# mapleCUx_large_340b-008.net
KiCad netlist of a schematic drawn in EAGLE
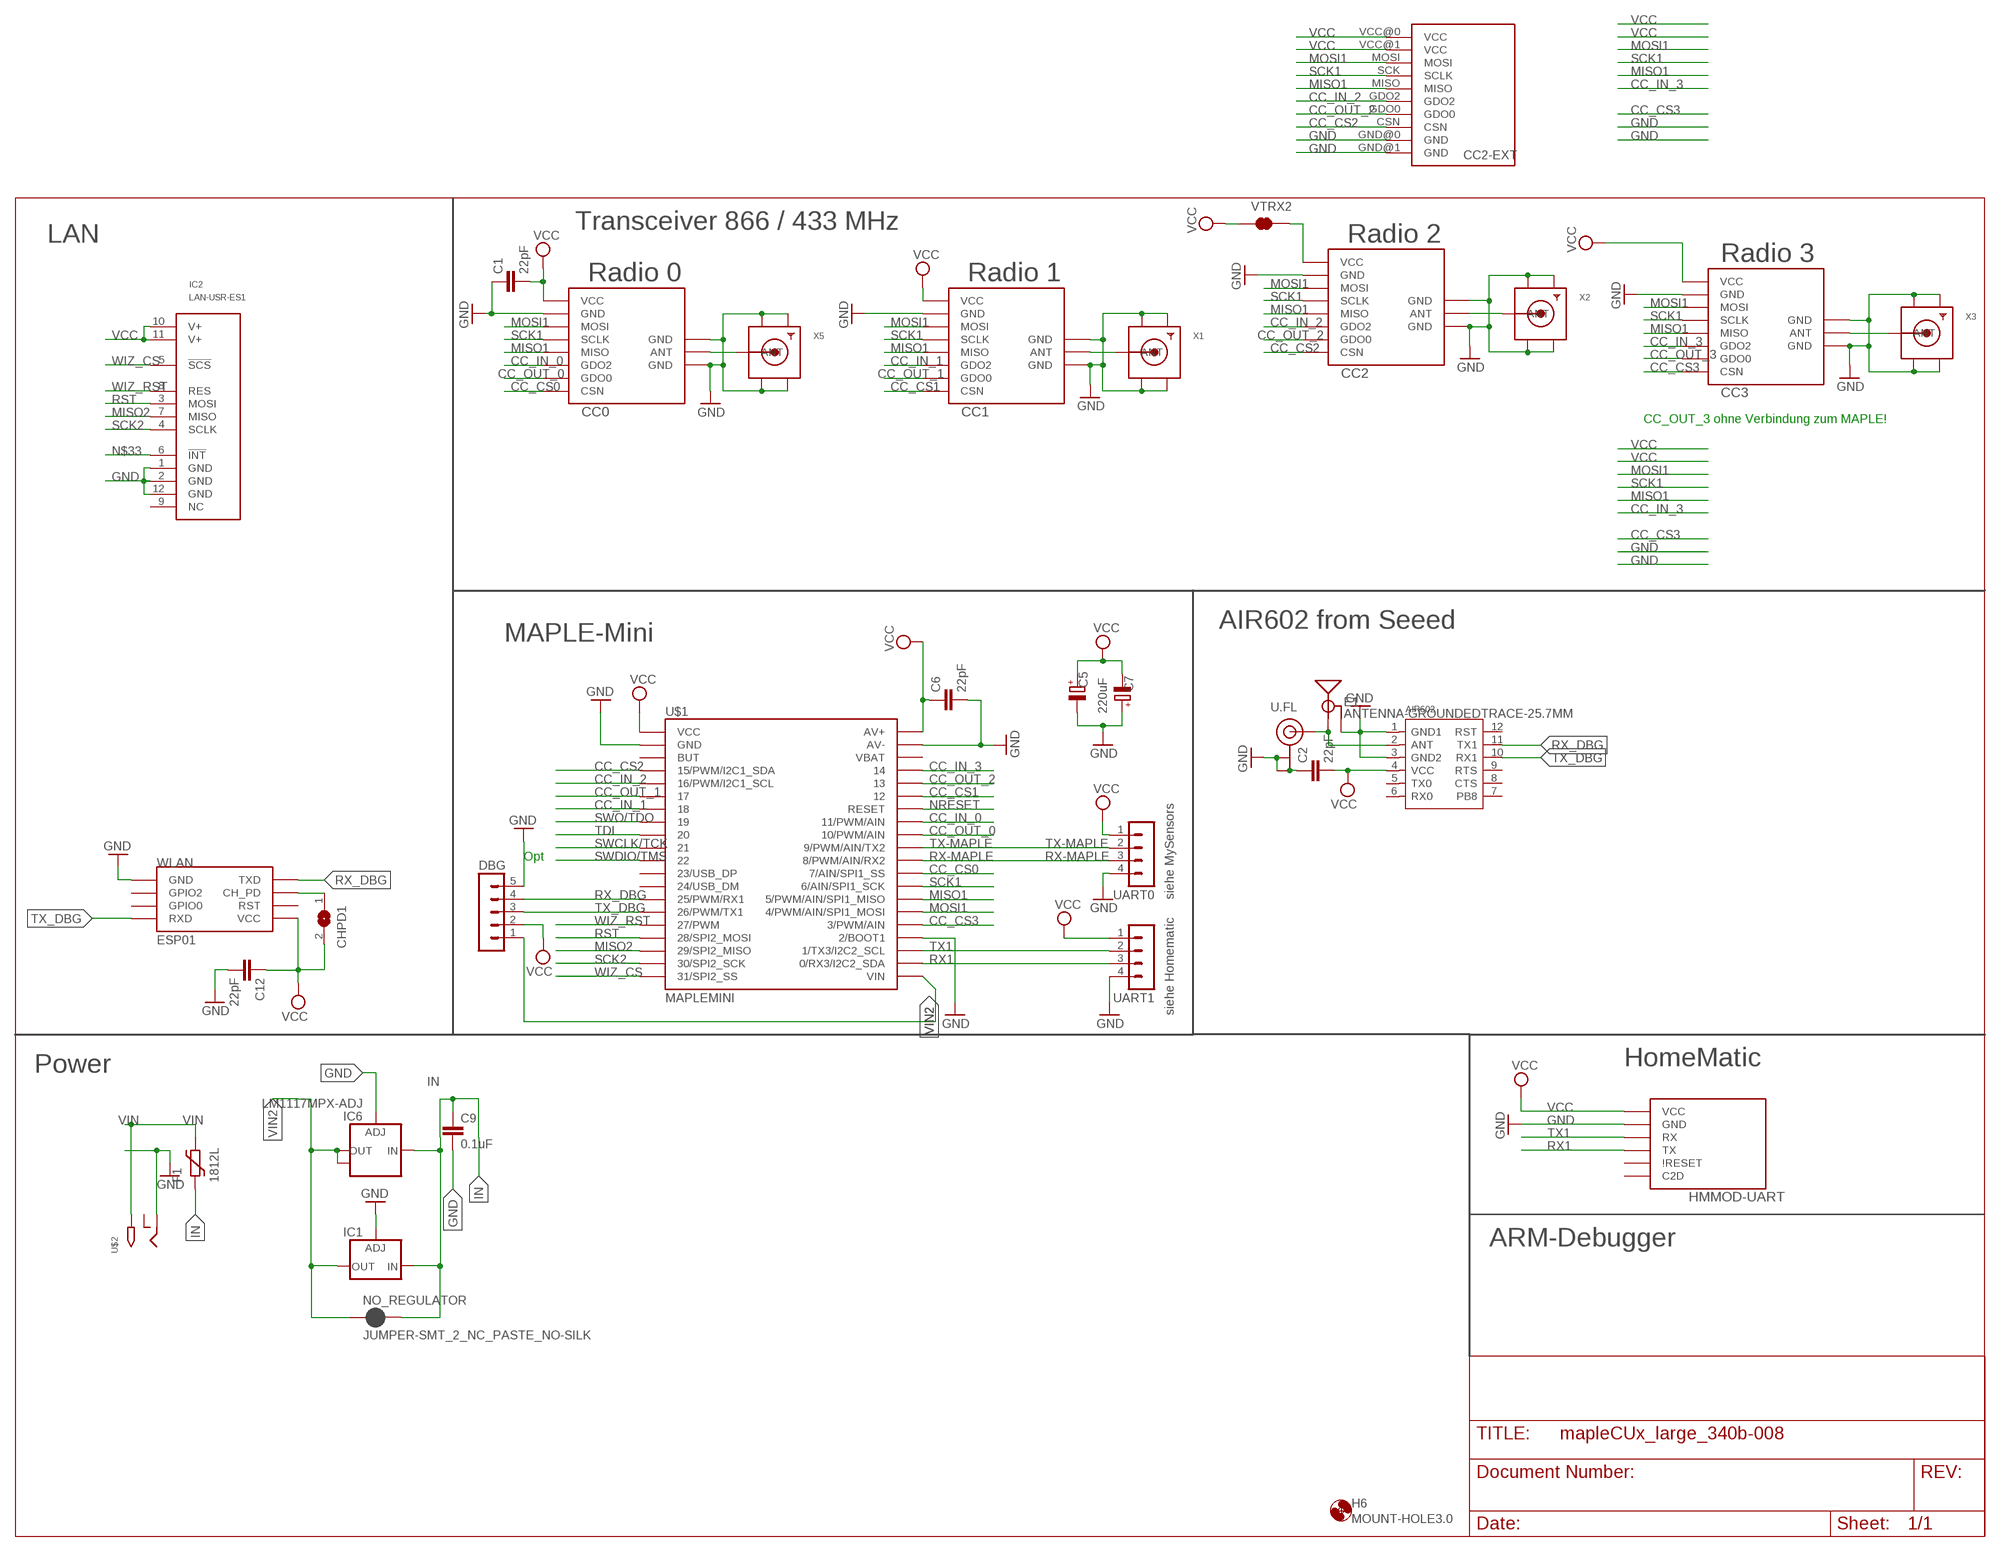
[diagram p0: schematic, sheet 1]

(export (version "E")
  (design (tool "Eeschema 10.0.6"))
  (components
    (comp (ref "AIR602")
      (value "AIR602")
      (footprint "eagle-import:MODULE12P-2.0-10X12MM")
      (libsource (lib "eagle-import") (part "AIR602"))
    )
    (comp (ref "C1")
      (value "22pF")
      (footprint "eagle-import:C0805")
      (libsource (lib "eagle-import") (part "C-EUC0805"))
    )
    (comp (ref "C2")
      (value "22pF")
      (footprint "eagle-import:C0805")
      (libsource (lib "eagle-import") (part "C-EUC0805"))
    )
    (comp (ref "C5")
      (value "220uF")
      (footprint "eagle-import:E5-8,5")
      (libsource (lib "eagle-import") (part "CPOL-EUE5-8.5"))
    )
    (comp (ref "C6")
      (value "22pF")
      (footprint "eagle-import:C0805")
      (libsource (lib "eagle-import") (part "C-EUC0805"))
    )
    (comp (ref "C7")
      (value "CPOL-EUSMCE")
      (footprint "eagle-import:SMC_E")
      (libsource (lib "eagle-import") (part "rcl_334_CPOL-EUSMCE"))
    )
    (comp (ref "C9")
      (value "0.1uF")
      (footprint "eagle-import:C1206")
      (libsource (lib "eagle-import") (part "C-EUC1206"))
    )
    (comp (ref "C12")
      (value "22pF")
      (footprint "eagle-import:C0805")
      (libsource (lib "eagle-import") (part "C-EUC0805"))
    )
    (comp (ref "CC0")
      (value "CC1101")
      (footprint "eagle-import:CC1101_MODULE1_SMD")
      (libsource (lib "eagle-import") (part "CC1101_MODULE1SMD"))
    )
    (comp (ref "CC1")
      (value "CC1101_MODULE1SMD")
      (footprint "eagle-import:CC1101_MODULE1_SMD")
      (libsource (lib "eagle-import") (part "CC1101_MODULE1SMD"))
    )
    (comp (ref "CC2")
      (value "CC1101_MODULE1SMD")
      (footprint "eagle-import:CC1101_MODULE1_SMD")
      (libsource (lib "eagle-import") (part "CC1101_MODULE1SMD"))
    )
    (comp (ref "CC2-EXT")
      (value "CC1101_MODULE3_DIL")
      (footprint "eagle-import:CC1101_MODULE3_DIL")
      (libsource (lib "eagle-import") (part "CC1101_MODULE3_DIL"))
    )
    (comp (ref "CC3")
      (value "CC1101_MODULE1SMD")
      (footprint "eagle-import:CC1101_MODULE1_SMD")
      (libsource (lib "eagle-import") (part "CC1101_MODULE1SMD"))
    )
    (comp (ref "CHPD1")
      (value "SJ")
      (footprint "eagle-import:SJ")
      (libsource (lib "eagle-import") (part "SJ"))
    )
    (comp (ref "DBG")
      (value "MA05-1")
      (footprint "eagle-import:MA05-1")
      (libsource (lib "eagle-import") (part "MA05-1"))
    )
    (comp (ref "E1")
      (value "ANTENNA-GROUNDEDTRACE-25.7MM")
      (footprint "eagle-import:TRACE_ANTENNA_2.4GHZ_25.7MM")
      (libsource (lib "eagle-import") (part "ANTENNA-GROUNDEDTRACE-25.7MM"))
    )
    (comp (ref "F1")
      (value "1812L")
      (footprint "eagle-import:1812L")
      (libsource (lib "eagle-import") (part "1812L"))
    )
    (comp (ref "H6")
      (value "MOUNT-HOLE3.0")
      (footprint "eagle-import:3,0")
      (libsource (lib "eagle-import") (part "MOUNT-HOLE3.0"))
    )
    (comp (ref "HMMOD-UART")
      (value "HM-MOD-UARTDIL")
      (footprint "eagle-import:HM-MOD-UART-DIL")
      (libsource (lib "eagle-import") (part "HM-MOD-UARTDIL"))
    )
    (comp (ref "IC1")
      (value "LD117ADT50TR")
      (footprint "eagle-import:DPACK")
      (libsource (lib "eagle-import") (part "LD117A?DT50TR"))
    )
    (comp (ref "IC2")
      (value "LAN-USR-ES1")
      (footprint "eagle-import:USR-ES1")
      (libsource (lib "eagle-import") (part "LAN-USR-ES1"))
    )
    (comp (ref "IC6")
      (value "LM1117MPX-ADJ")
      (footprint "eagle-import:SOT223")
      (libsource (lib "eagle-import") (part "LM1117MPX-ADJ"))
    )
    (comp (ref "NO_REGULATOR")
      (value "JUMPER-SMT_2_NC_PASTE_NO-SILK")
      (footprint "eagle-import:SMT-JUMPER_2_NC_PASTE_NO-SILK")
      (libsource (lib "eagle-import") (part "JUMPER-SMT_2_NC_PASTE_NO-SILK"))
    )
    (comp (ref "U$1")
      (value "MAPLEMINI")
      (footprint "eagle-import:20-DIP")
      (libsource (lib "eagle-import") (part "MAPLEMINI"))
    )
    (comp (ref "U$2")
      (value "2.1MMJACKTHM")
      (footprint "eagle-import:PJ-102A")
      (libsource (lib "eagle-import") (part "2.1MMJACKTHM"))
    )
    (comp (ref "U.FL")
      (value "U.FL")
      (footprint "eagle-import:U.FL")
      (libsource (lib "eagle-import") (part "U.FL"))
    )
    (comp (ref "UART0")
      (value "MA04-1")
      (footprint "eagle-import:MA04-1")
      (libsource (lib "eagle-import") (part "MA04-1"))
    )
    (comp (ref "UART1")
      (value "MA04-1")
      (footprint "eagle-import:MA04-1")
      (libsource (lib "eagle-import") (part "MA04-1"))
    )
    (comp (ref "VTRX2")
      (value "JUMPER-SMT_2_NC_TRACE_SILK")
      (footprint "eagle-import:SMT-JUMPER_2_NC_TRACE_SILK")
      (libsource (lib "eagle-import") (part "JUMPER-SMT_2_NC_TRACE_SILK"))
    )
    (comp (ref "WLAN")
      (value "ESP01")
      (footprint "eagle-import:ESP01")
      (libsource (lib "eagle-import") (part "ESP01"))
    )
    (comp (ref "X1")
      (value "SMACONNECTOR_EDGE")
      (footprint "eagle-import:SMA_EDGELAUNCH")
      (libsource (lib "eagle-import") (part "SMACONNECTOR_EDGE"))
    )
    (comp (ref "X2")
      (value "SMACONNECTOR_EDGE")
      (footprint "eagle-import:SMA_EDGELAUNCH")
      (libsource (lib "eagle-import") (part "SMACONNECTOR_EDGE"))
    )
    (comp (ref "X3")
      (value "SMACONNECTOR_EDGE")
      (footprint "eagle-import:SMA_EDGELAUNCH")
      (libsource (lib "eagle-import") (part "SMACONNECTOR_EDGE"))
    )
    (comp (ref "X5")
      (value "SMACONNECTOR_EDGE")
      (footprint "eagle-import:SMA_EDGELAUNCH")
      (libsource (lib "eagle-import") (part "SMACONNECTOR_EDGE"))
    )
  )
  (nets
    (net (code "1") (name "/CC_CS0") (class "Default")
      (node (ref "CC0") (pin "CSN") (pinfunction "CSN_CSN") (pintype "bidirectional"))
      (node (ref "U$1") (pin "29") (pinfunction "7/AIN/SPI1_SS_29") (pintype "bidirectional"))
    )
    (net (code "2") (name "/CC_CS1") (class "Default")
      (node (ref "CC1") (pin "CSN") (pinfunction "CSN_CSN") (pintype "bidirectional"))
      (node (ref "U$1") (pin "35") (pinfunction "12_35") (pintype "bidirectional"))
    )
    (net (code "3") (name "/CC_CS2") (class "Default")
      (node (ref "CC2") (pin "CSN") (pinfunction "CSN_CSN") (pintype "bidirectional"))
      (node (ref "CC2-EXT") (pin "CSN") (pinfunction "CSN_CSN") (pintype "bidirectional"))
      (node (ref "U$1") (pin "4") (pinfunction "15/PWM/I2C1_SDA_4") (pintype "bidirectional"))
    )
    (net (code "4") (name "/CC_CS3") (class "Default")
      (node (ref "CC3") (pin "CSN") (pinfunction "CSN_CSN") (pintype "bidirectional"))
      (node (ref "U$1") (pin "25") (pinfunction "3/PWM/AIN_25") (pintype "bidirectional"))
    )
    (net (code "5") (name "/CC_IN_0") (class "Default")
      (node (ref "CC0") (pin "GDO2") (pinfunction "GDO2_GDO2") (pintype "bidirectional"))
      (node (ref "U$1") (pin "33") (pinfunction "11/PWM/AIN_33") (pintype "bidirectional"))
    )
    (net (code "6") (name "/CC_IN_1") (class "Default")
      (node (ref "CC1") (pin "GDO2") (pinfunction "GDO2_GDO2") (pintype "bidirectional"))
      (node (ref "U$1") (pin "7") (pinfunction "18_7") (pintype "bidirectional"))
    )
    (net (code "7") (name "/CC_IN_2") (class "Default")
      (node (ref "CC2") (pin "GDO2") (pinfunction "GDO2_GDO2") (pintype "bidirectional"))
      (node (ref "CC2-EXT") (pin "GDO2") (pinfunction "GDO2_GDO2") (pintype "bidirectional"))
      (node (ref "U$1") (pin "5") (pinfunction "16/PWM/I2C1_SCL_5") (pintype "bidirectional"))
    )
    (net (code "8") (name "/CC_IN_3") (class "Default")
      (node (ref "CC3") (pin "GDO2") (pinfunction "GDO2_GDO2") (pintype "bidirectional"))
      (node (ref "U$1") (pin "37") (pinfunction "14_37") (pintype "bidirectional"))
    )
    (net (code "9") (name "/CC_OUT_0") (class "Default")
      (node (ref "CC0") (pin "GDO0") (pinfunction "GDO0_GDO0") (pintype "bidirectional"))
      (node (ref "U$1") (pin "32") (pinfunction "10/PWM/AIN_32") (pintype "bidirectional"))
    )
    (net (code "10") (name "/CC_OUT_1") (class "Default")
      (node (ref "CC1") (pin "GDO0") (pinfunction "GDO0_GDO0") (pintype "bidirectional"))
      (node (ref "U$1") (pin "6") (pinfunction "17_6") (pintype "bidirectional"))
    )
    (net (code "11") (name "/CC_OUT_2") (class "Default")
      (node (ref "CC2") (pin "GDO0") (pinfunction "GDO0_GDO0") (pintype "bidirectional"))
      (node (ref "CC2-EXT") (pin "GDO0") (pinfunction "GDO0_GDO0") (pintype "bidirectional"))
      (node (ref "U$1") (pin "36") (pinfunction "13_36") (pintype "bidirectional"))
    )
    (net (code "12") (name "/CC_OUT_3") (class "Default")
      (node (ref "CC3") (pin "GDO0") (pinfunction "GDO0_GDO0") (pintype "bidirectional"))
    )
    (net (code "13") (name "/MISO1") (class "Default")
      (node (ref "CC0") (pin "MISO") (pinfunction "MISO_MISO") (pintype "bidirectional"))
      (node (ref "CC1") (pin "MISO") (pinfunction "MISO_MISO") (pintype "bidirectional"))
      (node (ref "CC2") (pin "MISO") (pinfunction "MISO_MISO") (pintype "bidirectional"))
      (node (ref "CC2-EXT") (pin "MISO") (pinfunction "MISO_MISO") (pintype "bidirectional"))
      (node (ref "CC3") (pin "MISO") (pinfunction "MISO_MISO") (pintype "bidirectional"))
      (node (ref "U$1") (pin "27") (pinfunction "5/PWM/AIN/SPI1_MISO_27") (pintype "bidirectional"))
    )
    (net (code "14") (name "/MISO2") (class "Default")
      (node (ref "IC2") (pin "7") (pinfunction "MISO_7") (pintype "bidirectional"))
      (node (ref "U$1") (pin "18") (pinfunction "29/SPI2_MISO_18") (pintype "bidirectional"))
    )
    (net (code "15") (name "/MOSI1") (class "Default")
      (node (ref "CC0") (pin "MOSI") (pinfunction "MOSI_MOSI") (pintype "bidirectional"))
      (node (ref "CC1") (pin "MOSI") (pinfunction "MOSI_MOSI") (pintype "bidirectional"))
      (node (ref "CC2") (pin "MOSI") (pinfunction "MOSI_MOSI") (pintype "bidirectional"))
      (node (ref "CC2-EXT") (pin "MOSI") (pinfunction "MOSI_MOSI") (pintype "bidirectional"))
      (node (ref "CC3") (pin "MOSI") (pinfunction "MOSI_MOSI") (pintype "bidirectional"))
      (node (ref "U$1") (pin "26") (pinfunction "4/PWM/AIN/SPI1_MOSI_26") (pintype "bidirectional"))
    )
    (net (code "16") (name "/N$33") (class "Default")
      (node (ref "IC2") (pin "6") (pinfunction "~{INT}_6") (pintype "output"))
    )
    (net (code "17") (name "/NRESET") (class "Default")
      (node (ref "U$1") (pin "34") (pinfunction "RESET_34") (pintype "bidirectional"))
    )
    (net (code "18") (name "/RST") (class "Default")
      (node (ref "IC2") (pin "3") (pinfunction "MOSI_3") (pintype "bidirectional"))
      (node (ref "U$1") (pin "17") (pinfunction "28/SPI2_MOSI_17") (pintype "bidirectional"))
    )
    (net (code "19") (name "/RX-MAPLE") (class "Default")
      (node (ref "U$1") (pin "30") (pinfunction "8/PWM/AIN/RX2_30") (pintype "bidirectional"))
      (node (ref "UART0") (pin "3") (pinfunction "3_3") (pintype "passive"))
    )
    (net (code "20") (name "/RX1") (class "Default")
      (node (ref "HMMOD-UART") (pin "5") (pinfunction "TX_5") (pintype "bidirectional"))
      (node (ref "U$1") (pin "22") (pinfunction "0/RX3/I2C2_SDA_22") (pintype "bidirectional"))
      (node (ref "UART1") (pin "3") (pinfunction "3_3") (pintype "passive"))
    )
    (net (code "21") (name "/SCK1") (class "Default")
      (node (ref "CC0") (pin "SCLK") (pinfunction "SCLK_SCLK") (pintype "bidirectional"))
      (node (ref "CC1") (pin "SCLK") (pinfunction "SCLK_SCLK") (pintype "bidirectional"))
      (node (ref "CC2") (pin "SCLK") (pinfunction "SCLK_SCLK") (pintype "bidirectional"))
      (node (ref "CC2-EXT") (pin "SCK") (pinfunction "SCLK_SCK") (pintype "bidirectional"))
      (node (ref "CC3") (pin "SCLK") (pinfunction "SCLK_SCLK") (pintype "bidirectional"))
      (node (ref "U$1") (pin "28") (pinfunction "6/AIN/SPI1_SCK_28") (pintype "bidirectional"))
    )
    (net (code "22") (name "/SCK2") (class "Default")
      (node (ref "IC2") (pin "4") (pinfunction "SCLK_4") (pintype "input"))
      (node (ref "U$1") (pin "19") (pinfunction "30/SPI2_SCK_19") (pintype "bidirectional"))
    )
    (net (code "23") (name "/SWCLK{slash}TCK") (class "Default")
      (node (ref "U$1") (pin "10") (pinfunction "21_10") (pintype "bidirectional"))
    )
    (net (code "24") (name "/SWDIO{slash}TMS") (class "Default")
      (node (ref "U$1") (pin "11") (pinfunction "22_11") (pintype "bidirectional"))
    )
    (net (code "25") (name "/SWO{slash}TDO") (class "Default")
      (node (ref "U$1") (pin "8") (pinfunction "19_8") (pintype "bidirectional"))
    )
    (net (code "26") (name "/TDI") (class "Default")
      (node (ref "U$1") (pin "9") (pinfunction "20_9") (pintype "bidirectional"))
    )
    (net (code "27") (name "/TX-MAPLE") (class "Default")
      (node (ref "U$1") (pin "31") (pinfunction "9/PWM/AIN/TX2_31") (pintype "bidirectional"))
      (node (ref "UART0") (pin "2") (pinfunction "2_2") (pintype "passive"))
    )
    (net (code "28") (name "/TX1") (class "Default")
      (node (ref "HMMOD-UART") (pin "6") (pinfunction "RX_6") (pintype "bidirectional"))
      (node (ref "U$1") (pin "23") (pinfunction "1/TX3/I2C2_SCL_23") (pintype "bidirectional"))
      (node (ref "UART1") (pin "2") (pinfunction "2_2") (pintype "passive"))
    )
    (net (code "29") (name "/VIN") (class "Default")
      (node (ref "F1") (pin "P$2") (pinfunction "2_P$2") (pintype "passive"))
      (node (ref "U$2") (pin "TIP") (pinfunction "TIP_TIP") (pintype "bidirectional"))
    )
    (net (code "30") (name "/WIZ_CS") (class "Default")
      (node (ref "IC2") (pin "5") (pinfunction "~{SCS}_5") (pintype "input"))
      (node (ref "U$1") (pin "20") (pinfunction "31/SPI2_SS_20") (pintype "bidirectional"))
    )
    (net (code "31") (name "/WIZ_RST") (class "Default")
      (node (ref "IC2") (pin "8") (pinfunction "RES_8") (pintype "input"))
      (node (ref "U$1") (pin "16") (pinfunction "27/PWM_16") (pintype "bidirectional"))
    )
    (net (code "32") (name "GND") (class "Default")
      (node (ref "AIR602") (pin "1") (pinfunction "GND1_1") (pintype "bidirectional"))
      (node (ref "AIR602") (pin "3") (pinfunction "GND2_3") (pintype "bidirectional"))
      (node (ref "C1") (pin "1") (pinfunction "1_1") (pintype "passive"))
      (node (ref "C12") (pin "2") (pinfunction "2_2") (pintype "passive"))
      (node (ref "C5") (pin "-") (pinfunction "-_-") (pintype "passive"))
      (node (ref "C6") (pin "2") (pinfunction "2_2") (pintype "passive"))
      (node (ref "C7") (pin "+") (pinfunction "+_+") (pintype "passive"))
      (node (ref "C9") (pin "2") (pinfunction "2_2") (pintype "passive"))
      (node (ref "CC0") (pin "GND@0") (pinfunction "GND_GND@0") (pintype "power_in"))
      (node (ref "CC0") (pin "GND@1") (pinfunction "GND_GND@1") (pintype "power_in"))
      (node (ref "CC0") (pin "GND@2") (pinfunction "GND_GND@2") (pintype "power_in"))
      (node (ref "CC1") (pin "GND@0") (pinfunction "GND_GND@0") (pintype "power_in"))
      (node (ref "CC1") (pin "GND@1") (pinfunction "GND_GND@1") (pintype "power_in"))
      (node (ref "CC1") (pin "GND@2") (pinfunction "GND_GND@2") (pintype "power_in"))
      (node (ref "CC2") (pin "GND@0") (pinfunction "GND_GND@0") (pintype "power_in"))
      (node (ref "CC2") (pin "GND@1") (pinfunction "GND_GND@1") (pintype "power_in"))
      (node (ref "CC2") (pin "GND@2") (pinfunction "GND_GND@2") (pintype "power_in"))
      (node (ref "CC2-EXT") (pin "GND@0") (pinfunction "GND_GND@0") (pintype "power_in"))
      (node (ref "CC2-EXT") (pin "GND@1") (pinfunction "GND_GND@1") (pintype "power_in"))
      (node (ref "CC3") (pin "GND@0") (pinfunction "GND_GND@0") (pintype "power_in"))
      (node (ref "CC3") (pin "GND@1") (pinfunction "GND_GND@1") (pintype "power_in"))
      (node (ref "CC3") (pin "GND@2") (pinfunction "GND_GND@2") (pintype "power_in"))
      (node (ref "DBG") (pin "5") (pinfunction "5_5") (pintype "passive"))
      (node (ref "E1") (pin "GND") (pinfunction "GND_GND") (pintype "bidirectional"))
      (node (ref "E1") (pin "GND2") (pinfunction "GND_GND2") (pintype "bidirectional"))
      (node (ref "HMMOD-UART") (pin "2") (pinfunction "GND_2") (pintype "power_in"))
      (node (ref "IC1") (pin "1") (pinfunction "ADJ_1") (pintype "input"))
      (node (ref "IC2") (pin "1") (pinfunction "GND_1") (pintype "power_in"))
      (node (ref "IC2") (pin "12") (pinfunction "GND_12") (pintype "power_in"))
      (node (ref "IC2") (pin "2") (pinfunction "GND_2") (pintype "power_in"))
      (node (ref "IC6") (pin "1") (pinfunction "ADJ_1") (pintype "input"))
      (node (ref "U$1") (pin "2") (pinfunction "GND_2") (pintype "bidirectional"))
      (node (ref "U$1") (pin "24") (pinfunction "2/BOOT1_24") (pintype "bidirectional"))
      (node (ref "U$1") (pin "39") (pinfunction "AV-_39") (pintype "bidirectional"))
      (node (ref "U$2") (pin "RING") (pinfunction "RING_RING") (pintype "bidirectional"))
      (node (ref "U.FL") (pin "1") (pinfunction "GND_1") (pintype "bidirectional"))
      (node (ref "U.FL") (pin "2") (pinfunction "GND_2") (pintype "bidirectional"))
      (node (ref "UART0") (pin "4") (pinfunction "4_4") (pintype "passive"))
      (node (ref "UART1") (pin "4") (pinfunction "4_4") (pintype "passive"))
      (node (ref "WLAN") (pin "GND") (pinfunction "GND_GND") (pintype "bidirectional"))
      (node (ref "X1") (pin "GND@1") (pinfunction "GND4_GND@1") (pintype "power_in"))
      (node (ref "X1") (pin "GND@2") (pinfunction "GND3_GND@2") (pintype "power_in"))
      (node (ref "X1") (pin "GND@3") (pinfunction "GND2_GND@3") (pintype "power_in"))
      (node (ref "X1") (pin "GND@4") (pinfunction "GND1_GND@4") (pintype "power_in"))
      (node (ref "X2") (pin "GND@1") (pinfunction "GND4_GND@1") (pintype "power_in"))
      (node (ref "X2") (pin "GND@2") (pinfunction "GND3_GND@2") (pintype "power_in"))
      (node (ref "X2") (pin "GND@3") (pinfunction "GND2_GND@3") (pintype "power_in"))
      (node (ref "X2") (pin "GND@4") (pinfunction "GND1_GND@4") (pintype "power_in"))
      (node (ref "X3") (pin "GND@1") (pinfunction "GND4_GND@1") (pintype "power_in"))
      (node (ref "X3") (pin "GND@2") (pinfunction "GND3_GND@2") (pintype "power_in"))
      (node (ref "X3") (pin "GND@3") (pinfunction "GND2_GND@3") (pintype "power_in"))
      (node (ref "X3") (pin "GND@4") (pinfunction "GND1_GND@4") (pintype "power_in"))
      (node (ref "X5") (pin "GND@1") (pinfunction "GND4_GND@1") (pintype "power_in"))
      (node (ref "X5") (pin "GND@2") (pinfunction "GND3_GND@2") (pintype "power_in"))
      (node (ref "X5") (pin "GND@3") (pinfunction "GND2_GND@3") (pintype "power_in"))
      (node (ref "X5") (pin "GND@4") (pinfunction "GND1_GND@4") (pintype "power_in"))
    )
    (net (code "33") (name "IN") (class "Default")
      (node (ref "C9") (pin "1") (pinfunction "1_1") (pintype "passive"))
      (node (ref "F1") (pin "P$1") (pinfunction "1_P$1") (pintype "passive"))
      (node (ref "IC1") (pin "3") (pinfunction "IN_3") (pintype "input"))
      (node (ref "IC6") (pin "3") (pinfunction "IN_3") (pintype "input"))
      (node (ref "NO_REGULATOR") (pin "2") (pinfunction "2_2") (pintype "passive"))
    )
    (net (code "34") (name "Net-(AIR602-ANT)") (class "Default")
      (node (ref "AIR602") (pin "2") (pinfunction "ANT_2") (pintype "bidirectional"))
      (node (ref "E1") (pin "ANT") (pinfunction "SIGNAL_ANT") (pintype "bidirectional"))
      (node (ref "U.FL") (pin "FEED") (pinfunction "SIGNAL_FEED") (pintype "bidirectional"))
    )
    (net (code "35") (name "Net-(CC2-PadVCC)") (class "Default")
      (node (ref "CC2") (pin "VCC") (pinfunction "VCC_VCC") (pintype "power_in"))
      (node (ref "VTRX2") (pin "2") (pinfunction "2_2") (pintype "passive"))
    )
    (net (code "36") (name "Net-(CHPD1-Pad1)") (class "Default")
      (node (ref "CHPD1") (pin "1") (pinfunction "1_1") (pintype "passive"))
      (node (ref "WLAN") (pin "CH_PD") (pinfunction "CH_PD_CH_PD") (pintype "bidirectional"))
    )
    (net (code "37") (name "Net-(X1-ANT)") (class "Default")
      (node (ref "CC1") (pin "ANT") (pinfunction "ANT_ANT") (pintype "output"))
      (node (ref "X1") (pin "P") (pinfunction "ANT_P") (pintype "bidirectional"))
    )
    (net (code "38") (name "Net-(X2-ANT)") (class "Default")
      (node (ref "CC2") (pin "ANT") (pinfunction "ANT_ANT") (pintype "output"))
      (node (ref "X2") (pin "P") (pinfunction "ANT_P") (pintype "bidirectional"))
    )
    (net (code "39") (name "Net-(X3-ANT)") (class "Default")
      (node (ref "CC3") (pin "ANT") (pinfunction "ANT_ANT") (pintype "output"))
      (node (ref "X3") (pin "P") (pinfunction "ANT_P") (pintype "bidirectional"))
    )
    (net (code "40") (name "Net-(X5-ANT)") (class "Default")
      (node (ref "CC0") (pin "ANT") (pinfunction "ANT_ANT") (pintype "output"))
      (node (ref "X5") (pin "P") (pinfunction "ANT_P") (pintype "bidirectional"))
    )
    (net (code "41") (name "RX_DBG") (class "Default")
      (node (ref "AIR602") (pin "11") (pinfunction "TX1_11") (pintype "bidirectional"))
      (node (ref "DBG") (pin "4") (pinfunction "4_4") (pintype "passive"))
      (node (ref "U$1") (pin "14") (pinfunction "25/PWM/RX1_14") (pintype "bidirectional"))
      (node (ref "WLAN") (pin "TX") (pinfunction "TXD_TX") (pintype "bidirectional"))
    )
    (net (code "42") (name "TX_DBG") (class "Default")
      (node (ref "AIR602") (pin "10") (pinfunction "RX1_10") (pintype "bidirectional"))
      (node (ref "DBG") (pin "3") (pinfunction "3_3") (pintype "passive"))
      (node (ref "U$1") (pin "15") (pinfunction "26/PWM/TX1_15") (pintype "bidirectional"))
      (node (ref "WLAN") (pin "RX") (pinfunction "RXD_RX") (pintype "bidirectional"))
    )
    (net (code "43") (name "VCC") (class "Default")
      (node (ref "AIR602") (pin "4") (pinfunction "VCC_4") (pintype "bidirectional"))
      (node (ref "C1") (pin "2") (pinfunction "2_2") (pintype "passive"))
      (node (ref "C12") (pin "1") (pinfunction "1_1") (pintype "passive"))
      (node (ref "C2") (pin "2") (pinfunction "2_2") (pintype "passive"))
      (node (ref "C5") (pin "+") (pinfunction "+_+") (pintype "passive"))
      (node (ref "C6") (pin "1") (pinfunction "1_1") (pintype "passive"))
      (node (ref "C7") (pin "-") (pinfunction "-_-") (pintype "passive"))
      (node (ref "CC0") (pin "VCC") (pinfunction "VCC_VCC") (pintype "power_in"))
      (node (ref "CC1") (pin "VCC") (pinfunction "VCC_VCC") (pintype "power_in"))
      (node (ref "CC2-EXT") (pin "VCC@0") (pinfunction "VCC_VCC@0") (pintype "power_in"))
      (node (ref "CC2-EXT") (pin "VCC@1") (pinfunction "VCC_VCC@1") (pintype "power_in"))
      (node (ref "CC3") (pin "VCC") (pinfunction "VCC_VCC") (pintype "power_in"))
      (node (ref "CHPD1") (pin "2") (pinfunction "2_2") (pintype "passive"))
      (node (ref "DBG") (pin "2") (pinfunction "2_2") (pintype "passive"))
      (node (ref "HMMOD-UART") (pin "1") (pinfunction "VCC_1") (pintype "power_in"))
      (node (ref "IC2") (pin "10") (pinfunction "V+_10") (pintype "power_in"))
      (node (ref "IC2") (pin "11") (pinfunction "V+_11") (pintype "power_in"))
      (node (ref "U$1") (pin "1") (pinfunction "VCC_1") (pintype "bidirectional"))
      (node (ref "U$1") (pin "40") (pinfunction "AV+_40") (pintype "bidirectional"))
      (node (ref "UART0") (pin "1") (pinfunction "1_1") (pintype "passive"))
      (node (ref "UART1") (pin "1") (pinfunction "1_1") (pintype "passive"))
      (node (ref "VTRX2") (pin "1") (pinfunction "1_1") (pintype "passive"))
      (node (ref "WLAN") (pin "VCC") (pinfunction "VCC_VCC") (pintype "bidirectional"))
    )
    (net (code "44") (name "VIN2") (class "Default")
      (node (ref "DBG") (pin "1") (pinfunction "1_1") (pintype "passive"))
      (node (ref "IC1") (pin "4") (pinfunction "OUT_4") (pintype "passive"))
      (node (ref "IC6") (pin "2") (pinfunction "OUT_2") (pintype "passive"))
      (node (ref "IC6") (pin "TAB") (pinfunction "OUT1_TAB") (pintype "passive"))
      (node (ref "NO_REGULATOR") (pin "1") (pinfunction "1_1") (pintype "passive"))
      (node (ref "U$1") (pin "21") (pinfunction "VIN_21") (pintype "bidirectional"))
    )
    (net (code "45") (name "unconnected-(AIR602-CTS-Pad8)") (class "Default")
      (node (ref "AIR602") (pin "8") (pinfunction "CTS_8") (pintype "bidirectional"))
    )
    (net (code "46") (name "unconnected-(AIR602-PB8-Pad7)") (class "Default")
      (node (ref "AIR602") (pin "7") (pinfunction "PB8_7") (pintype "bidirectional"))
    )
    (net (code "47") (name "unconnected-(AIR602-RST-Pad12)") (class "Default")
      (node (ref "AIR602") (pin "12") (pinfunction "RST_12") (pintype "bidirectional"))
    )
    (net (code "48") (name "unconnected-(AIR602-RTS-Pad9)") (class "Default")
      (node (ref "AIR602") (pin "9") (pinfunction "RTS_9") (pintype "bidirectional"))
    )
    (net (code "49") (name "unconnected-(AIR602-RX0-Pad6)") (class "Default")
      (node (ref "AIR602") (pin "6") (pinfunction "RX0_6") (pintype "bidirectional"))
    )
    (net (code "50") (name "unconnected-(AIR602-TX0-Pad5)") (class "Default")
      (node (ref "AIR602") (pin "5") (pinfunction "TX0_5") (pintype "bidirectional"))
    )
    (net (code "51") (name "unconnected-(C2-Pad1)") (class "Default")
      (node (ref "C2") (pin "1") (pinfunction "1_1") (pintype "passive"))
    )
    (net (code "52") (name "unconnected-(HMMOD-UART-C2D-Pad3)") (class "Default")
      (node (ref "HMMOD-UART") (pin "3") (pinfunction "C2D_3") (pintype "bidirectional"))
    )
    (net (code "53") (name "unconnected-(HMMOD-UART-\\~{RESET}-Pad4)") (class "Default")
      (node (ref "HMMOD-UART") (pin "4") (pinfunction "\\~{RESET}_4") (pintype "bidirectional"))
    )
    (net (code "54") (name "unconnected-(IC2-NC-Pad9)") (class "Default")
      (node (ref "IC2") (pin "9") (pinfunction "NC_9") (pintype "no_connect"))
    )
    (net (code "55") (name "unconnected-(U$1-23{slash}USB_DP-Pad12)") (class "Default")
      (node (ref "U$1") (pin "12") (pinfunction "23/USB_DP_12") (pintype "bidirectional"))
    )
    (net (code "56") (name "unconnected-(U$1-24{slash}USB_DM-Pad13)") (class "Default")
      (node (ref "U$1") (pin "13") (pinfunction "24/USB_DM_13") (pintype "bidirectional"))
    )
    (net (code "57") (name "unconnected-(U$1-BUT-Pad3)") (class "Default")
      (node (ref "U$1") (pin "3") (pinfunction "BUT_3") (pintype "bidirectional"))
    )
    (net (code "58") (name "unconnected-(U$1-VBAT-Pad38)") (class "Default")
      (node (ref "U$1") (pin "38") (pinfunction "VBAT_38") (pintype "bidirectional"))
    )
    (net (code "59") (name "unconnected-(U$2-PadRING_SW)") (class "Default")
      (node (ref "U$2") (pin "RING_SW") (pinfunction "RING_SW_RING_SW") (pintype "bidirectional"))
    )
    (net (code "60") (name "unconnected-(WLAN-PadGPIO0)") (class "Default")
      (node (ref "WLAN") (pin "GPIO0") (pinfunction "GPIO0_GPIO0") (pintype "bidirectional"))
    )
    (net (code "61") (name "unconnected-(WLAN-PadGPIO2)") (class "Default")
      (node (ref "WLAN") (pin "GPIO2") (pinfunction "GPIO2_GPIO2") (pintype "bidirectional"))
    )
    (net (code "62") (name "unconnected-(WLAN-PadRST)") (class "Default")
      (node (ref "WLAN") (pin "RST") (pinfunction "RST_RST") (pintype "bidirectional"))
    )
  )
)
